# RadioHTC_STM_v3_top_cpu.net
KiCad netlist of a schematic drawn in EAGLE
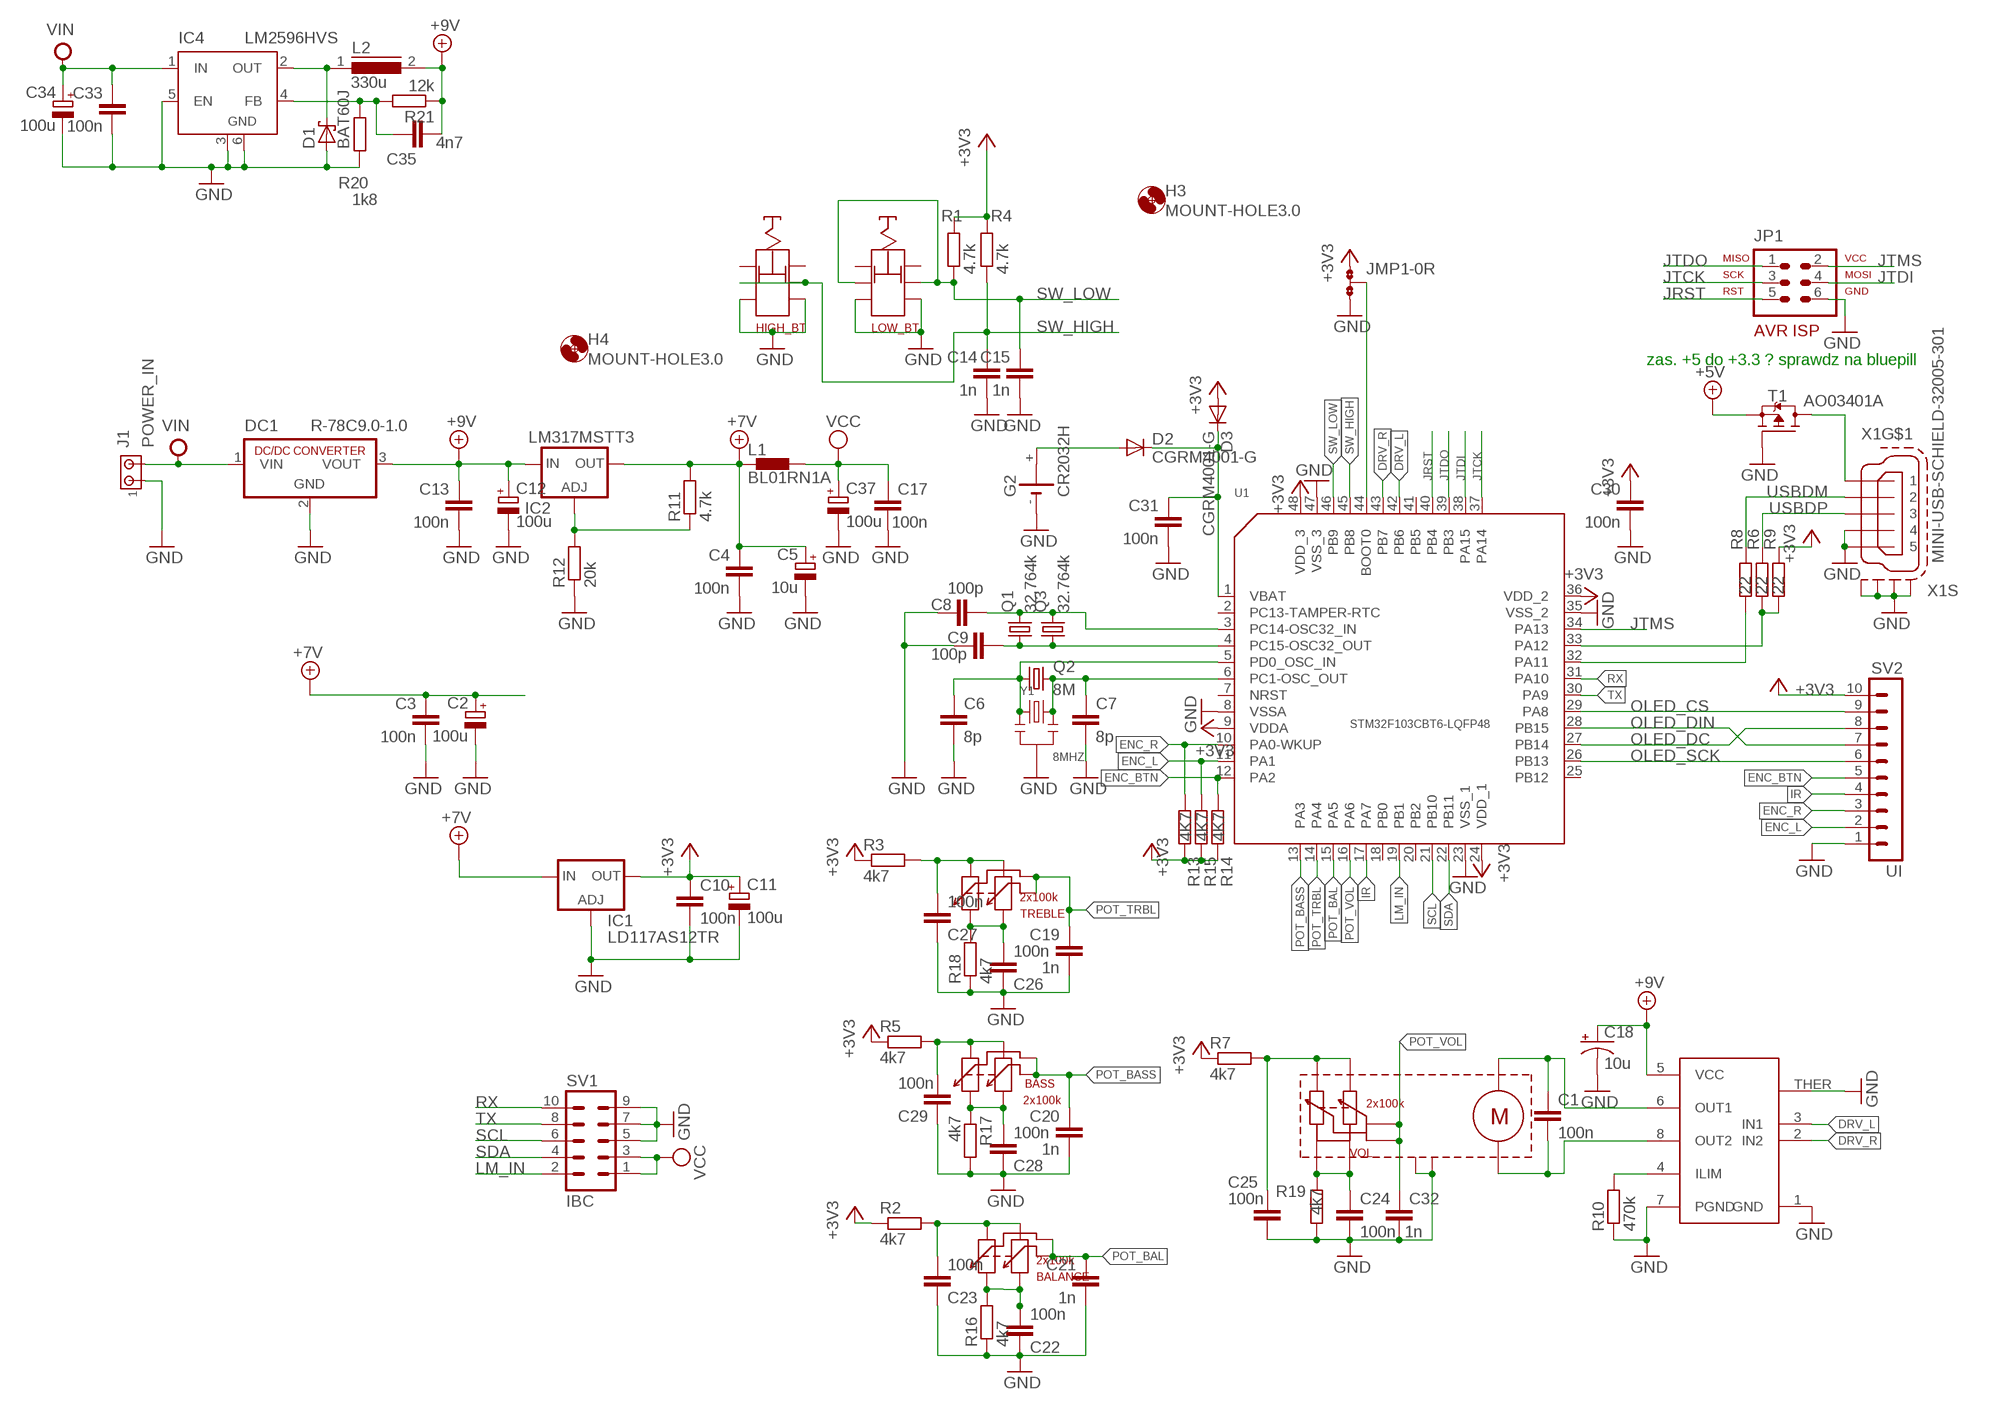
[diagram p0: schematic, sheet 1]

(export (version "E")
  (design (tool "Eeschema 10.0.6"))
  (components
    (comp (ref "BALANCE")
      (value "2x100k")
      (footprint "eagle-import:POT_VERT_DOUBLE")
      (libsource (lib "eagle-import") (part "POT_TONSIL"))
    )
    (comp (ref "BASS")
      (value "2x100k")
      (footprint "eagle-import:POT_VERT_DOUBLE")
      (libsource (lib "eagle-import") (part "POT_TONSIL"))
    )
    (comp (ref "C1")
      (value "100n")
      (footprint "eagle-import:C1206")
      (libsource (lib "eagle-import") (part "C-EUC1206"))
    )
    (comp (ref "C2")
      (value "100u")
      (footprint "eagle-import:E2-5")
      (libsource (lib "eagle-import") (part "CPOL-EUE2-5"))
    )
    (comp (ref "C3")
      (value "100n")
      (footprint "eagle-import:C1206")
      (libsource (lib "eagle-import") (part "C-EUC1206"))
    )
    (comp (ref "C4")
      (value "100n")
      (footprint "eagle-import:C1206")
      (libsource (lib "eagle-import") (part "C-EUC1206"))
    )
    (comp (ref "C5")
      (value "10u")
      (footprint "eagle-import:E2-5")
      (libsource (lib "eagle-import") (part "CPOL-EUE2-5"))
    )
    (comp (ref "C6")
      (value "8p")
      (footprint "eagle-import:C0805K")
      (libsource (lib "eagle-import") (part "C-EUC0805K"))
    )
    (comp (ref "C7")
      (value "8p")
      (footprint "eagle-import:C0805K")
      (libsource (lib "eagle-import") (part "C-EUC0805K"))
    )
    (comp (ref "C8")
      (value "100p")
      (footprint "eagle-import:C0805K")
      (libsource (lib "eagle-import") (part "C-EUC0805K"))
    )
    (comp (ref "C9")
      (value "100p")
      (footprint "eagle-import:C0805K")
      (libsource (lib "eagle-import") (part "C-EUC0805K"))
    )
    (comp (ref "C10")
      (value "100n")
      (footprint "eagle-import:C1206")
      (libsource (lib "eagle-import") (part "C-EUC1206"))
    )
    (comp (ref "C11")
      (value "100u")
      (footprint "eagle-import:E2-5")
      (libsource (lib "eagle-import") (part "CPOL-EUE2-5"))
    )
    (comp (ref "C12")
      (value "100u")
      (footprint "eagle-import:153CLV-0605")
      (libsource (lib "eagle-import") (part "CPOL-EU153CLV-0605"))
    )
    (comp (ref "C13")
      (value "100n")
      (footprint "eagle-import:C1206")
      (libsource (lib "eagle-import") (part "C-EUC1206"))
    )
    (comp (ref "C14")
      (value "1n")
      (footprint "eagle-import:C1206")
      (libsource (lib "eagle-import") (part "C-EUC1206"))
    )
    (comp (ref "C15")
      (value "1n")
      (footprint "eagle-import:C1206")
      (libsource (lib "eagle-import") (part "C-EUC1206"))
    )
    (comp (ref "C17")
      (value "100n")
      (footprint "eagle-import:C1206")
      (libsource (lib "eagle-import") (part "C-EUC1206"))
    )
    (comp (ref "C18")
      (value "10u")
      (footprint "eagle-import:153CLV-0810")
      (libsource (lib "eagle-import") (part "CPOL-US153CLV-0810"))
    )
    (comp (ref "C19")
      (value "1n")
      (footprint "eagle-import:C1206")
      (libsource (lib "eagle-import") (part "C-EUC1206"))
    )
    (comp (ref "C20")
      (value "1n")
      (footprint "eagle-import:C1206")
      (libsource (lib "eagle-import") (part "C-EUC1206"))
    )
    (comp (ref "C21")
      (value "1n")
      (footprint "eagle-import:C1206")
      (libsource (lib "eagle-import") (part "C-EUC1206"))
    )
    (comp (ref "C22")
      (value "100n")
      (footprint "eagle-import:C1206")
      (libsource (lib "eagle-import") (part "C-EUC1206"))
    )
    (comp (ref "C23")
      (value "100n")
      (footprint "eagle-import:C1206")
      (libsource (lib "eagle-import") (part "C-EUC1206"))
    )
    (comp (ref "C24")
      (value "100n")
      (footprint "eagle-import:C1206")
      (libsource (lib "eagle-import") (part "C-EUC1206"))
    )
    (comp (ref "C25")
      (value "100n")
      (footprint "eagle-import:C1206")
      (libsource (lib "eagle-import") (part "C-EUC1206"))
    )
    (comp (ref "C26")
      (value "100n")
      (footprint "eagle-import:C1206")
      (libsource (lib "eagle-import") (part "C-EUC1206"))
    )
    (comp (ref "C27")
      (value "100n")
      (footprint "eagle-import:C1206")
      (libsource (lib "eagle-import") (part "C-EUC1206"))
    )
    (comp (ref "C28")
      (value "100n")
      (footprint "eagle-import:C1206")
      (libsource (lib "eagle-import") (part "C-EUC1206"))
    )
    (comp (ref "C29")
      (value "100n")
      (footprint "eagle-import:C1206")
      (libsource (lib "eagle-import") (part "C-EUC1206"))
    )
    (comp (ref "C30")
      (value "100n")
      (footprint "eagle-import:C1206")
      (libsource (lib "eagle-import") (part "C-EUC1206"))
    )
    (comp (ref "C31")
      (value "100n")
      (footprint "eagle-import:C1206")
      (libsource (lib "eagle-import") (part "C-EUC1206"))
    )
    (comp (ref "C32")
      (value "1n")
      (footprint "eagle-import:C1206")
      (libsource (lib "eagle-import") (part "C-EUC1206"))
    )
    (comp (ref "C33")
      (value "100n")
      (footprint "eagle-import:C1206")
      (libsource (lib "eagle-import") (part "C-EUC1206"))
    )
    (comp (ref "C34")
      (value "100u")
      (footprint "eagle-import:E2-5")
      (libsource (lib "eagle-import") (part "CPOL-EUE2-5"))
    )
    (comp (ref "C35")
      (value "4n7")
      (footprint "eagle-import:C1206")
      (libsource (lib "eagle-import") (part "C-EUC1206"))
    )
    (comp (ref "C37")
      (value "100u")
      (footprint "eagle-import:153CLV-0405")
      (libsource (lib "eagle-import") (part "CPOL-EU153CLV-0405"))
    )
    (comp (ref "D1")
      (value "BAT60J")
      (footprint "eagle-import:SOD323_ST")
      (libsource (lib "eagle-import") (part "BAT60J"))
    )
    (comp (ref "D2")
      (value "CGRM4001-G")
      (footprint "eagle-import:SOD-123_MINI-SMA")
      (libsource (lib "eagle-import") (part "CGRM400-G1"))
    )
    (comp (ref "D3")
      (value "CGRM4001-G")
      (footprint "eagle-import:SOD-123_MINI-SMA")
      (libsource (lib "eagle-import") (part "CGRM400-G1"))
    )
    (comp (ref "DC1")
      (value "R-78C9.0-1.0")
      (footprint "eagle-import:SIP3")
      (libsource (lib "eagle-import") (part "R-78C-1.09.0"))
    )
    (comp (ref "G2")
      (value "CR2032H")
      (footprint "eagle-import:CR2032H")
      (libsource (lib "eagle-import") (part "CR2032H"))
    )
    (comp (ref "H3")
      (value "MOUNT-HOLE3.0")
      (footprint "eagle-import:3,0")
      (libsource (lib "eagle-import") (part "MOUNT-HOLE3.0"))
    )
    (comp (ref "H4")
      (value "MOUNT-HOLE3.0")
      (footprint "eagle-import:3,0")
      (libsource (lib "eagle-import") (part "MOUNT-HOLE3.0"))
    )
    (comp (ref "IC1")
      (value "LD117AS12TR")
      (footprint "eagle-import:SOT223")
      (libsource (lib "eagle-import") (part "LD117A?S12TR"))
    )
    (comp (ref "IC2")
      (value "LM317MSTT3")
      (footprint "eagle-import:SOT223")
      (libsource (lib "eagle-import") (part "LM317?MSTT3"))
    )
    (comp (ref "IC4")
      (value "LM2596HVS")
      (footprint "eagle-import:TO263-5")
      (libsource (lib "eagle-import") (part "LM2596S"))
    )
    (comp (ref "J1")
      (value "POWER_IN")
      (footprint "eagle-import:1X2MTA")
      (libsource (lib "eagle-import") (part "MTA02-156"))
    )
    (comp (ref "JMP1")
      (value "0R-JUMPA")
      (footprint "eagle-import:A0R-JMP")
      (libsource (lib "eagle-import") (part "0R-JUMPA"))
    )
    (comp (ref "JP1")
      (value "AVR-ISP-6VERT")
      (footprint "eagle-import:AVR-ISP-6")
      (libsource (lib "eagle-import") (part "AVR-ISP-6VERT"))
    )
    (comp (ref "L1")
      (value "BL01RN1A")
      (footprint "eagle-import:BL01RN1A")
      (libsource (lib "eagle-import") (part "BL01RN1A"))
    )
    (comp (ref "L2")
      (value "330u")
      (footprint "eagle-import:DR74")
      (libsource (lib "eagle-import") (part "DR74"))
    )
    (comp (ref "Q1")
      (value "32.764k")
      (footprint "eagle-import:MM39SL")
      (libsource (lib "eagle-import") (part "CRYSTALMM39SL"))
    )
    (comp (ref "Q2")
      (value "8M")
      (footprint "eagle-import:HC49U-V")
      (libsource (lib "eagle-import") (part "CRYSTALHC49U-V"))
    )
    (comp (ref "Q3")
      (value "32.764k")
      (footprint "eagle-import:MM20SS")
      (libsource (lib "eagle-import") (part "CRYSTALMM20SS"))
    )
    (comp (ref "R1")
      (value "4.7k")
      (footprint "eagle-import:R1206")
      (libsource (lib "eagle-import") (part "R-EU_R1206"))
    )
    (comp (ref "R2")
      (value "4k7")
      (footprint "eagle-import:R1206")
      (libsource (lib "eagle-import") (part "R-EU_R1206"))
    )
    (comp (ref "R3")
      (value "4k7")
      (footprint "eagle-import:R1206")
      (libsource (lib "eagle-import") (part "R-EU_R1206"))
    )
    (comp (ref "R4")
      (value "4.7k")
      (footprint "eagle-import:R1206")
      (libsource (lib "eagle-import") (part "R-EU_R1206"))
    )
    (comp (ref "R5")
      (value "4k7")
      (footprint "eagle-import:R1206")
      (libsource (lib "eagle-import") (part "R-EU_R1206"))
    )
    (comp (ref "R6")
      (value "22")
      (footprint "eagle-import:R1206")
      (libsource (lib "eagle-import") (part "R-EU_R1206"))
    )
    (comp (ref "R7")
      (value "4k7")
      (footprint "eagle-import:R1206")
      (libsource (lib "eagle-import") (part "R-EU_R1206"))
    )
    (comp (ref "R8")
      (value "22")
      (footprint "eagle-import:R1206")
      (libsource (lib "eagle-import") (part "R-EU_R1206"))
    )
    (comp (ref "R9")
      (value "22")
      (footprint "eagle-import:R1206")
      (libsource (lib "eagle-import") (part "R-EU_R1206"))
    )
    (comp (ref "R10")
      (value "470k")
      (footprint "eagle-import:R1206")
      (libsource (lib "eagle-import") (part "R-EU_R1206"))
    )
    (comp (ref "R11")
      (value "4.7k")
      (footprint "eagle-import:R1206")
      (libsource (lib "eagle-import") (part "R-EU_R1206"))
    )
    (comp (ref "R12")
      (value "20k")
      (footprint "eagle-import:R1206")
      (libsource (lib "eagle-import") (part "R-EU_R1206"))
    )
    (comp (ref "R13")
      (value "4K7")
      (footprint "eagle-import:R1206")
      (libsource (lib "eagle-import") (part "R-EU_R1206"))
    )
    (comp (ref "R14")
      (value "4K7")
      (footprint "eagle-import:R1206")
      (libsource (lib "eagle-import") (part "R-EU_R1206"))
    )
    (comp (ref "R15")
      (value "4K7")
      (footprint "eagle-import:R1206")
      (libsource (lib "eagle-import") (part "R-EU_R1206"))
    )
    (comp (ref "R16")
      (value "4k7")
      (footprint "eagle-import:R1206")
      (libsource (lib "eagle-import") (part "R-EU_R1206"))
    )
    (comp (ref "R17")
      (value "4k7")
      (footprint "eagle-import:R1206")
      (libsource (lib "eagle-import") (part "R-EU_R1206"))
    )
    (comp (ref "R18")
      (value "4k7")
      (footprint "eagle-import:R1206")
      (libsource (lib "eagle-import") (part "R-EU_R1206"))
    )
    (comp (ref "R19")
      (value "4k7")
      (footprint "eagle-import:R1206")
      (libsource (lib "eagle-import") (part "R-EU_R1206"))
    )
    (comp (ref "R20")
      (value "1k8")
      (footprint "eagle-import:R1206")
      (libsource (lib "eagle-import") (part "R-EU_R1206"))
    )
    (comp (ref "R21")
      (value "12k")
      (footprint "eagle-import:R1206")
      (libsource (lib "eagle-import") (part "R-EU_R1206"))
    )
    (comp (ref "SV1")
      (value "IBC")
      (footprint "eagle-import:ML10")
      (libsource (lib "eagle-import") (part "ML10"))
    )
    (comp (ref "SV2")
      (value "UI")
      (footprint "eagle-import:MA10-1W")
      (libsource (lib "eagle-import") (part "MA10-1W"))
    )
    (comp (ref "SW4")
      (value "LOW_BT")
      (footprint "eagle-import:ISO3")
      (libsource (lib "eagle-import") (part "ISO3"))
    )
    (comp (ref "SW6")
      (value "HIGH_BT")
      (footprint "eagle-import:ISO3")
      (libsource (lib "eagle-import") (part "ISO3"))
    )
    (comp (ref "T1")
      (value "AO03401A")
      (footprint "eagle-import:SOT23-R")
      (libsource (lib "eagle-import") (part "P-MOSFET"))
    )
    (comp (ref "TREBLE")
      (value "2x100k")
      (footprint "eagle-import:POT_VERT_DOUBLE")
      (libsource (lib "eagle-import") (part "POT_TONSIL"))
    )
    (comp (ref "U1")
      (value "STM32F103CBT6-LQFP48")
      (footprint "eagle-import:LQFP48-0.5-7X7MM")
      (fields (field (name "MPN") "STM32F103CBT6"))
      (libsource (lib "eagle-import") (part "MCU-STM32F103CBT6(LQFP48)"))
    )
    (comp (ref "U2")
      (value "DRV8871")
      (footprint "eagle-import:DRV8871")
      (libsource (lib "eagle-import") (part "DRV8871"))
    )
    (comp (ref "VOL")
      (value "2x100k")
      (footprint "eagle-import:POT_DOUBLE_MOTOR")
      (libsource (lib "eagle-import") (part "POT_DOUBLE_MOTOR"))
    )
    (comp (ref "X1")
      (value "MINI-USB-SCHIELD-32005-301")
      (footprint "eagle-import:32005-301")
      (libsource (lib "eagle-import") (part "MINI-USB-SCHIELD-32005-301"))
    )
    (comp (ref "Y1")
      (value "8MHZ")
      (footprint "eagle-import:X3-SMD-3.6X1.3X0.8MM")
      (fields (field (name "MPN") "CSTCE16M0V53-R0"))
      (libsource (lib "eagle-import") (part "SMD-RESONATOR-16MHZ-15PF-0.5%-40R(3P-3.2X1.3MM)"))
    )
  )
  (nets
    (net (code "1") (name "+3V3") (class "Default")
      (node (ref "C10") (pin "1") (pinfunction "1_1") (pintype "passive"))
      (node (ref "C11") (pin "+") (pinfunction "+_+") (pintype "passive"))
      (node (ref "C30") (pin "1") (pinfunction "1_1") (pintype "passive"))
      (node (ref "D3") (pin "A") (pinfunction "A_A") (pintype "passive"))
      (node (ref "IC1") (pin "4") (pinfunction "OUT_4") (pintype "passive"))
      (node (ref "JMP1") (pin "1") (pinfunction "1_1") (pintype "passive"))
      (node (ref "R1") (pin "2") (pinfunction "2_2") (pintype "passive"))
      (node (ref "R13") (pin "2") (pinfunction "2_2") (pintype "passive"))
      (node (ref "R14") (pin "2") (pinfunction "2_2") (pintype "passive"))
      (node (ref "R15") (pin "2") (pinfunction "2_2") (pintype "passive"))
      (node (ref "R2") (pin "1") (pinfunction "1_1") (pintype "passive"))
      (node (ref "R3") (pin "1") (pinfunction "1_1") (pintype "passive"))
      (node (ref "R4") (pin "2") (pinfunction "2_2") (pintype "passive"))
      (node (ref "R5") (pin "1") (pinfunction "1_1") (pintype "passive"))
      (node (ref "R7") (pin "1") (pinfunction "1_1") (pintype "passive"))
      (node (ref "R9") (pin "2") (pinfunction "2_2") (pintype "passive"))
      (node (ref "SV2") (pin "10") (pinfunction "10_10") (pintype "passive"))
      (node (ref "U1") (pin "24") (pinfunction "VDD_1_24") (pintype "bidirectional"))
      (node (ref "U1") (pin "36") (pinfunction "VDD_2_36") (pintype "bidirectional"))
      (node (ref "U1") (pin "48") (pinfunction "VDD_3_48") (pintype "bidirectional"))
      (node (ref "U1") (pin "9") (pinfunction "VDDA_9") (pintype "bidirectional"))
    )
    (net (code "2") (name "+5V") (class "Default")
      (node (ref "T1") (pin "2") (pinfunction "S_2") (pintype "passive"))
    )
    (net (code "3") (name "+7V") (class "Default")
      (node (ref "C2") (pin "+") (pinfunction "+_+") (pintype "passive"))
      (node (ref "C3") (pin "1") (pinfunction "1_1") (pintype "passive"))
      (node (ref "C4") (pin "1") (pinfunction "1_1") (pintype "passive"))
      (node (ref "C5") (pin "+") (pinfunction "+_+") (pintype "passive"))
      (node (ref "IC1") (pin "3") (pinfunction "IN_3") (pintype "input"))
      (node (ref "IC2") (pin "4") (pinfunction "OUT_4") (pintype "passive"))
      (node (ref "L1") (pin "1") (pinfunction "1_1") (pintype "passive"))
      (node (ref "R11") (pin "2") (pinfunction "2_2") (pintype "passive"))
    )
    (net (code "4") (name "+9V") (class "Default")
      (node (ref "C12") (pin "+") (pinfunction "+_+") (pintype "passive"))
      (node (ref "C13") (pin "1") (pinfunction "1_1") (pintype "passive"))
      (node (ref "C18") (pin "+") (pinfunction "+_+") (pintype "passive"))
      (node (ref "C35") (pin "2") (pinfunction "2_2") (pintype "passive"))
      (node (ref "DC1") (pin "3") (pinfunction "VOUT_3") (pintype "passive"))
      (node (ref "IC2") (pin "3") (pinfunction "IN_3") (pintype "input"))
      (node (ref "L2") (pin "2") (pinfunction "2_2") (pintype "passive"))
      (node (ref "R21") (pin "1") (pinfunction "1_1") (pintype "passive"))
      (node (ref "U2") (pin "5") (pinfunction "VCC_5") (pintype "power_in"))
    )
    (net (code "5") (name "/JRST") (class "Default")
      (node (ref "JP1") (pin "5") (pinfunction "5_5") (pintype "passive"))
      (node (ref "U1") (pin "40") (pinfunction "PB4_40") (pintype "bidirectional"))
    )
    (net (code "6") (name "/JTCK") (class "Default")
      (node (ref "JP1") (pin "3") (pinfunction "3_3") (pintype "passive"))
      (node (ref "U1") (pin "37") (pinfunction "PA14_37") (pintype "bidirectional"))
    )
    (net (code "7") (name "/JTDI") (class "Default")
      (node (ref "JP1") (pin "4") (pinfunction "4_4") (pintype "passive"))
      (node (ref "U1") (pin "38") (pinfunction "PA15_38") (pintype "bidirectional"))
    )
    (net (code "8") (name "/JTDO") (class "Default")
      (node (ref "JP1") (pin "1") (pinfunction "1_1") (pintype "passive"))
      (node (ref "U1") (pin "39") (pinfunction "PB3_39") (pintype "bidirectional"))
    )
    (net (code "9") (name "/JTMS") (class "Default")
      (node (ref "JP1") (pin "2") (pinfunction "2_2") (pintype "passive"))
      (node (ref "U1") (pin "34") (pinfunction "PA13_34") (pintype "bidirectional"))
    )
    (net (code "10") (name "/OLED_CS") (class "Default")
      (node (ref "SV2") (pin "9") (pinfunction "9_9") (pintype "passive"))
      (node (ref "U1") (pin "29") (pinfunction "PA8_29") (pintype "bidirectional"))
    )
    (net (code "11") (name "/OLED_DC") (class "Default")
      (node (ref "SV2") (pin "8") (pinfunction "8_8") (pintype "passive"))
      (node (ref "U1") (pin "27") (pinfunction "PB14_27") (pintype "bidirectional"))
    )
    (net (code "12") (name "/OLED_DIN") (class "Default")
      (node (ref "SV2") (pin "7") (pinfunction "7_7") (pintype "passive"))
      (node (ref "U1") (pin "28") (pinfunction "PB15_28") (pintype "bidirectional"))
    )
    (net (code "13") (name "/OLED_SCK") (class "Default")
      (node (ref "SV2") (pin "6") (pinfunction "6_6") (pintype "passive"))
      (node (ref "U1") (pin "26") (pinfunction "PB13_26") (pintype "bidirectional"))
    )
    (net (code "14") (name "/USBDM") (class "Default")
      (node (ref "R8") (pin "2") (pinfunction "2_2") (pintype "passive"))
      (node (ref "X1") (pin "2") (pinfunction "2_2") (pintype "passive"))
    )
    (net (code "15") (name "/USBDP") (class "Default")
      (node (ref "R6") (pin "2") (pinfunction "2_2") (pintype "passive"))
      (node (ref "X1") (pin "3") (pinfunction "3_3") (pintype "passive"))
    )
    (net (code "16") (name "DRV_L") (class "Default")
      (node (ref "U1") (pin "42") (pinfunction "PB6_42") (pintype "bidirectional"))
      (node (ref "U2") (pin "3") (pinfunction "IN1_3") (pintype "input"))
    )
    (net (code "17") (name "DRV_R") (class "Default")
      (node (ref "U1") (pin "43") (pinfunction "PB7_43") (pintype "bidirectional"))
      (node (ref "U2") (pin "2") (pinfunction "IN2_2") (pintype "input"))
    )
    (net (code "18") (name "ENC_BTN") (class "Default")
      (node (ref "R14") (pin "1") (pinfunction "1_1") (pintype "passive"))
      (node (ref "SV2") (pin "5") (pinfunction "5_5") (pintype "passive"))
      (node (ref "U1") (pin "12") (pinfunction "PA2_12") (pintype "bidirectional"))
    )
    (net (code "19") (name "ENC_L") (class "Default")
      (node (ref "R15") (pin "1") (pinfunction "1_1") (pintype "passive"))
      (node (ref "SV2") (pin "2") (pinfunction "2_2") (pintype "passive"))
      (node (ref "U1") (pin "11") (pinfunction "PA1_11") (pintype "bidirectional"))
    )
    (net (code "20") (name "ENC_R") (class "Default")
      (node (ref "R13") (pin "1") (pinfunction "1_1") (pintype "passive"))
      (node (ref "SV2") (pin "3") (pinfunction "3_3") (pintype "passive"))
      (node (ref "U1") (pin "10") (pinfunction "PA0-WKUP_10") (pintype "bidirectional"))
    )
    (net (code "21") (name "GND") (class "Default")
      (node (ref "C10") (pin "2") (pinfunction "2_2") (pintype "passive"))
      (node (ref "C11") (pin "-") (pinfunction "-_-") (pintype "passive"))
      (node (ref "C12") (pin "-") (pinfunction "-_-") (pintype "passive"))
      (node (ref "C13") (pin "2") (pinfunction "2_2") (pintype "passive"))
      (node (ref "C14") (pin "2") (pinfunction "2_2") (pintype "passive"))
      (node (ref "C15") (pin "2") (pinfunction "2_2") (pintype "passive"))
      (node (ref "C17") (pin "2") (pinfunction "2_2") (pintype "passive"))
      (node (ref "C18") (pin "-") (pinfunction "-_-") (pintype "passive"))
      (node (ref "C19") (pin "2") (pinfunction "2_2") (pintype "passive"))
      (node (ref "C2") (pin "-") (pinfunction "-_-") (pintype "passive"))
      (node (ref "C20") (pin "2") (pinfunction "2_2") (pintype "passive"))
      (node (ref "C21") (pin "2") (pinfunction "2_2") (pintype "passive"))
      (node (ref "C22") (pin "1") (pinfunction "1_1") (pintype "passive"))
      (node (ref "C23") (pin "1") (pinfunction "1_1") (pintype "passive"))
      (node (ref "C24") (pin "1") (pinfunction "1_1") (pintype "passive"))
      (node (ref "C25") (pin "1") (pinfunction "1_1") (pintype "passive"))
      (node (ref "C26") (pin "1") (pinfunction "1_1") (pintype "passive"))
      (node (ref "C27") (pin "1") (pinfunction "1_1") (pintype "passive"))
      (node (ref "C28") (pin "1") (pinfunction "1_1") (pintype "passive"))
      (node (ref "C29") (pin "1") (pinfunction "1_1") (pintype "passive"))
      (node (ref "C3") (pin "2") (pinfunction "2_2") (pintype "passive"))
      (node (ref "C30") (pin "2") (pinfunction "2_2") (pintype "passive"))
      (node (ref "C31") (pin "2") (pinfunction "2_2") (pintype "passive"))
      (node (ref "C32") (pin "2") (pinfunction "2_2") (pintype "passive"))
      (node (ref "C33") (pin "2") (pinfunction "2_2") (pintype "passive"))
      (node (ref "C34") (pin "-") (pinfunction "-_-") (pintype "passive"))
      (node (ref "C37") (pin "-") (pinfunction "-_-") (pintype "passive"))
      (node (ref "C4") (pin "2") (pinfunction "2_2") (pintype "passive"))
      (node (ref "C5") (pin "-") (pinfunction "-_-") (pintype "passive"))
      (node (ref "C6") (pin "2") (pinfunction "2_2") (pintype "passive"))
      (node (ref "C7") (pin "2") (pinfunction "2_2") (pintype "passive"))
      (node (ref "C8") (pin "2") (pinfunction "2_2") (pintype "passive"))
      (node (ref "C9") (pin "1") (pinfunction "1_1") (pintype "passive"))
      (node (ref "D1") (pin "A") (pinfunction "A_A") (pintype "passive"))
      (node (ref "DC1") (pin "2") (pinfunction "GND_2") (pintype "passive"))
      (node (ref "G2") (pin "-") (pinfunction "-_-") (pintype "passive"))
      (node (ref "IC1") (pin "1") (pinfunction "ADJ_1") (pintype "input"))
      (node (ref "IC4") (pin "3") (pinfunction "GND_3") (pintype "power_in"))
      (node (ref "IC4") (pin "5") (pinfunction "EN_5") (pintype "input"))
      (node (ref "IC4") (pin "6") (pinfunction "GND_6") (pintype "power_in"))
      (node (ref "J1") (pin "1") (pinfunction "1_1") (pintype "passive"))
      (node (ref "JMP1") (pin "3") (pinfunction "3_3") (pintype "passive"))
      (node (ref "JP1") (pin "6") (pinfunction "6_6") (pintype "passive"))
      (node (ref "R10") (pin "1") (pinfunction "1_1") (pintype "passive"))
      (node (ref "R12") (pin "1") (pinfunction "1_1") (pintype "passive"))
      (node (ref "R16") (pin "1") (pinfunction "1_1") (pintype "passive"))
      (node (ref "R17") (pin "2") (pinfunction "2_2") (pintype "passive"))
      (node (ref "R18") (pin "1") (pinfunction "1_1") (pintype "passive"))
      (node (ref "R19") (pin "1") (pinfunction "1_1") (pintype "passive"))
      (node (ref "R20") (pin "1") (pinfunction "1_1") (pintype "passive"))
      (node (ref "SV1") (pin "5") (pinfunction "5_5") (pintype "passive"))
      (node (ref "SV1") (pin "7") (pinfunction "7_7") (pintype "passive"))
      (node (ref "SV1") (pin "9") (pinfunction "9_9") (pintype "passive"))
      (node (ref "SV2") (pin "1") (pinfunction "1_1") (pintype "passive"))
      (node (ref "SW4") (pin "P$3") (pinfunction "P$3_P$3") (pintype "bidirectional"))
      (node (ref "SW4") (pin "P$4") (pinfunction "P$4_P$4") (pintype "bidirectional"))
      (node (ref "SW6") (pin "P$3") (pinfunction "P$3_P$3") (pintype "bidirectional"))
      (node (ref "SW6") (pin "P$4") (pinfunction "P$4_P$4") (pintype "bidirectional"))
      (node (ref "T1") (pin "1") (pinfunction "G_1") (pintype "passive"))
      (node (ref "U1") (pin "23") (pinfunction "VSS_1_23") (pintype "bidirectional"))
      (node (ref "U1") (pin "35") (pinfunction "VSS_2_35") (pintype "bidirectional"))
      (node (ref "U1") (pin "47") (pinfunction "VSS_3_47") (pintype "bidirectional"))
      (node (ref "U1") (pin "8") (pinfunction "VSSA_8") (pintype "bidirectional"))
      (node (ref "U2") (pin "1") (pinfunction "GND_1") (pintype "power_in"))
      (node (ref "U2") (pin "7") (pinfunction "PGND_7") (pintype "power_in"))
      (node (ref "U2") (pin "THER") (pinfunction "GND_THER") (pintype "power_in"))
      (node (ref "VOL") (pin "P$10") (pinfunction "G_P$10") (pintype "bidirectional"))
      (node (ref "VOL") (pin "P$9") (pinfunction "G_P$9") (pintype "bidirectional"))
      (node (ref "X1") (pin "4") (pinfunction "4_4") (pintype "passive"))
      (node (ref "X1") (pin "5") (pinfunction "5_5") (pintype "passive"))
      (node (ref "X1") (pin "M1") (pinfunction "S1_M1") (pintype "passive"))
      (node (ref "X1") (pin "M2") (pinfunction "S2_M2") (pintype "passive"))
      (node (ref "X1") (pin "M3") (pinfunction "S3_M3") (pintype "passive"))
      (node (ref "X1") (pin "M4") (pinfunction "S4_M4") (pintype "passive"))
      (node (ref "Y1") (pin "2") (pinfunction "2_2") (pintype "passive"))
    )
    (net (code "22") (name "IR") (class "Default")
      (node (ref "SV2") (pin "4") (pinfunction "4_4") (pintype "passive"))
      (node (ref "U1") (pin "17") (pinfunction "PA7_17") (pintype "bidirectional"))
    )
    (net (code "23") (name "LM_IN") (class "Default")
      (node (ref "SV1") (pin "2") (pinfunction "2_2") (pintype "passive"))
      (node (ref "U1") (pin "19") (pinfunction "PB1_19") (pintype "bidirectional"))
    )
    (net (code "24") (name "Net-(BALANCE-PadA1)") (class "Default")
      (node (ref "BALANCE") (pin "A1") (pinfunction "A1_A1") (pintype "passive"))
      (node (ref "BALANCE") (pin "A2") (pinfunction "A2_A2") (pintype "passive"))
      (node (ref "C23") (pin "2") (pinfunction "2_2") (pintype "passive"))
      (node (ref "R2") (pin "2") (pinfunction "2_2") (pintype "passive"))
    )
    (net (code "25") (name "Net-(BALANCE-PadB1)") (class "Default")
      (node (ref "BALANCE") (pin "B1") (pinfunction "B1_B1") (pintype "passive"))
      (node (ref "BALANCE") (pin "B2") (pinfunction "B2_B2") (pintype "passive"))
      (node (ref "C22") (pin "2") (pinfunction "2_2") (pintype "passive"))
      (node (ref "R16") (pin "2") (pinfunction "2_2") (pintype "passive"))
    )
    (net (code "26") (name "Net-(BASS-PadA1)") (class "Default")
      (node (ref "BASS") (pin "A1") (pinfunction "A1_A1") (pintype "passive"))
      (node (ref "BASS") (pin "A2") (pinfunction "A2_A2") (pintype "passive"))
      (node (ref "C29") (pin "2") (pinfunction "2_2") (pintype "passive"))
      (node (ref "R5") (pin "2") (pinfunction "2_2") (pintype "passive"))
    )
    (net (code "27") (name "Net-(BASS-PadB1)") (class "Default")
      (node (ref "BASS") (pin "B1") (pinfunction "B1_B1") (pintype "passive"))
      (node (ref "BASS") (pin "B2") (pinfunction "B2_B2") (pintype "passive"))
      (node (ref "C28") (pin "2") (pinfunction "2_2") (pintype "passive"))
      (node (ref "R17") (pin "1") (pinfunction "1_1") (pintype "passive"))
    )
    (net (code "28") (name "Net-(C24-Pad2)") (class "Default")
      (node (ref "C24") (pin "2") (pinfunction "2_2") (pintype "passive"))
      (node (ref "R19") (pin "2") (pinfunction "2_2") (pintype "passive"))
      (node (ref "VOL") (pin "P$5") (pinfunction "P$5_P$5") (pintype "passive"))
      (node (ref "VOL") (pin "P$6") (pinfunction "P$6_P$6") (pintype "passive"))
    )
    (net (code "29") (name "Net-(C25-Pad2)") (class "Default")
      (node (ref "C25") (pin "2") (pinfunction "2_2") (pintype "passive"))
      (node (ref "R7") (pin "2") (pinfunction "2_2") (pintype "passive"))
      (node (ref "VOL") (pin "P$2") (pinfunction "P$2_P$2") (pintype "passive"))
      (node (ref "VOL") (pin "P$3") (pinfunction "P$3_P$3") (pintype "passive"))
    )
    (net (code "30") (name "Net-(C26-Pad2)") (class "Default")
      (node (ref "C26") (pin "2") (pinfunction "2_2") (pintype "passive"))
      (node (ref "R18") (pin "2") (pinfunction "2_2") (pintype "passive"))
      (node (ref "TREBLE") (pin "B1") (pinfunction "B1_B1") (pintype "passive"))
      (node (ref "TREBLE") (pin "B2") (pinfunction "B2_B2") (pintype "passive"))
    )
    (net (code "31") (name "Net-(C27-Pad2)") (class "Default")
      (node (ref "C27") (pin "2") (pinfunction "2_2") (pintype "passive"))
      (node (ref "R3") (pin "2") (pinfunction "2_2") (pintype "passive"))
      (node (ref "TREBLE") (pin "A1") (pinfunction "A1_A1") (pintype "passive"))
      (node (ref "TREBLE") (pin "A2") (pinfunction "A2_A2") (pintype "passive"))
    )
    (net (code "32") (name "Net-(D2-PadA)") (class "Default")
      (node (ref "D2") (pin "A") (pinfunction "A_A") (pintype "passive"))
      (node (ref "G2") (pin "+") (pinfunction "+_+") (pintype "passive"))
    )
    (net (code "33") (name "Net-(IC2-ADJ)") (class "Default")
      (node (ref "IC2") (pin "1") (pinfunction "ADJ_1") (pintype "input"))
      (node (ref "R11") (pin "1") (pinfunction "1_1") (pintype "passive"))
      (node (ref "R12") (pin "2") (pinfunction "2_2") (pintype "passive"))
    )
    (net (code "34") (name "Net-(IC4-FB)") (class "Default")
      (node (ref "C35") (pin "1") (pinfunction "1_1") (pintype "passive"))
      (node (ref "IC4") (pin "4") (pinfunction "FB_4") (pintype "input"))
      (node (ref "R20") (pin "2") (pinfunction "2_2") (pintype "passive"))
      (node (ref "R21") (pin "2") (pinfunction "2_2") (pintype "passive"))
    )
    (net (code "35") (name "Net-(IC4-OUT)") (class "Default")
      (node (ref "D1") (pin "C") (pinfunction "C_C") (pintype "passive"))
      (node (ref "IC4") (pin "2") (pinfunction "OUT_2") (pintype "output"))
      (node (ref "L2") (pin "1") (pinfunction "1_1") (pintype "passive"))
    )
    (net (code "36") (name "Net-(Q1-2)") (class "Default")
      (node (ref "C8") (pin "1") (pinfunction "1_1") (pintype "passive"))
      (node (ref "Q1") (pin "4") (pinfunction "2_4") (pintype "passive"))
      (node (ref "Q3") (pin "4") (pinfunction "2_4") (pintype "passive"))
      (node (ref "U1") (pin "3") (pinfunction "PC14-OSC32_IN_3") (pintype "bidirectional"))
    )
    (net (code "37") (name "Net-(T1-D)") (class "Default")
      (node (ref "T1") (pin "3") (pinfunction "D_3") (pintype "passive"))
      (node (ref "X1") (pin "1") (pinfunction "1_1") (pintype "passive"))
    )
    (net (code "38") (name "Net-(U1-BOOT0)") (class "Default")
      (node (ref "JMP1") (pin "2") (pinfunction "2_2") (pintype "passive"))
      (node (ref "U1") (pin "44") (pinfunction "BOOT0_44") (pintype "bidirectional"))
    )
    (net (code "39") (name "Net-(U1-PA11)") (class "Default")
      (node (ref "R8") (pin "1") (pinfunction "1_1") (pintype "passive"))
      (node (ref "U1") (pin "32") (pinfunction "PA11_32") (pintype "bidirectional"))
    )
    (net (code "40") (name "Net-(U1-PA12)") (class "Default")
      (node (ref "R6") (pin "1") (pinfunction "1_1") (pintype "passive"))
      (node (ref "R9") (pin "1") (pinfunction "1_1") (pintype "passive"))
      (node (ref "U1") (pin "33") (pinfunction "PA12_33") (pintype "bidirectional"))
    )
    (net (code "41") (name "Net-(U1-PC1-OSC_OUT)") (class "Default")
      (node (ref "C7") (pin "1") (pinfunction "1_1") (pintype "passive"))
      (node (ref "Q2") (pin "2") (pinfunction "2_2") (pintype "passive"))
      (node (ref "U1") (pin "6") (pinfunction "PC1-OSC_OUT_6") (pintype "bidirectional"))
      (node (ref "Y1") (pin "3") (pinfunction "3_3") (pintype "passive"))
    )
    (net (code "42") (name "Net-(U1-PC15-OSC32_OUT)") (class "Default")
      (node (ref "C9") (pin "2") (pinfunction "2_2") (pintype "passive"))
      (node (ref "Q1") (pin "1") (pinfunction "1_1") (pintype "passive"))
      (node (ref "Q3") (pin "1") (pinfunction "1_1") (pintype "passive"))
      (node (ref "U1") (pin "4") (pinfunction "PC15-OSC32_OUT_4") (pintype "bidirectional"))
    )
    (net (code "43") (name "Net-(U1-PD0_OSC_IN)") (class "Default")
      (node (ref "C6") (pin "1") (pinfunction "1_1") (pintype "passive"))
      (node (ref "Q2") (pin "1") (pinfunction "1_1") (pintype "passive"))
      (node (ref "U1") (pin "5") (pinfunction "PD0_OSC_IN_5") (pintype "bidirectional"))
      (node (ref "Y1") (pin "1") (pinfunction "1_1") (pintype "passive"))
    )
    (net (code "44") (name "Net-(U1-VBAT)") (class "Default")
      (node (ref "C31") (pin "1") (pinfunction "1_1") (pintype "passive"))
      (node (ref "D2") (pin "C") (pinfunction "C_C") (pintype "passive"))
      (node (ref "D3") (pin "C") (pinfunction "C_C") (pintype "passive"))
      (node (ref "U1") (pin "1") (pinfunction "VBAT_1") (pintype "bidirectional"))
    )
    (net (code "45") (name "Net-(U2-ILIM)") (class "Default")
      (node (ref "R10") (pin "2") (pinfunction "2_2") (pintype "passive"))
      (node (ref "U2") (pin "4") (pinfunction "ILIM_4") (pintype "output"))
    )
    (net (code "46") (name "Net-(U2-OUT1)") (class "Default")
      (node (ref "C1") (pin "1") (pinfunction "1_1") (pintype "passive"))
      (node (ref "U2") (pin "6") (pinfunction "OUT1_6") (pintype "output"))
      (node (ref "VOL") (pin "M+") (pinfunction "M+_M+") (pintype "bidirectional"))
    )
    (net (code "47") (name "Net-(U2-OUT2)") (class "Default")
      (node (ref "C1") (pin "2") (pinfunction "2_2") (pintype "passive"))
      (node (ref "U2") (pin "8") (pinfunction "OUT2_8") (pintype "output"))
      (node (ref "VOL") (pin "M-") (pinfunction "M-_M-") (pintype "bidirectional"))
    )
    (net (code "48") (name "POT_BAL") (class "Default")
      (node (ref "BALANCE") (pin "C1") (pinfunction "C1_C1") (pintype "passive"))
      (node (ref "BALANCE") (pin "C2") (pinfunction "C2_C2") (pintype "passive"))
      (node (ref "C21") (pin "1") (pinfunction "1_1") (pintype "passive"))
      (node (ref "U1") (pin "15") (pinfunction "PA5_15") (pintype "bidirectional"))
    )
    (net (code "49") (name "POT_BASS") (class "Default")
      (node (ref "BASS") (pin "C1") (pinfunction "C1_C1") (pintype "passive"))
      (node (ref "BASS") (pin "C2") (pinfunction "C2_C2") (pintype "passive"))
      (node (ref "C20") (pin "1") (pinfunction "1_1") (pintype "passive"))
      (node (ref "U1") (pin "13") (pinfunction "PA3_13") (pintype "bidirectional"))
    )
    (net (code "50") (name "POT_TRBL") (class "Default")
      (node (ref "C19") (pin "1") (pinfunction "1_1") (pintype "passive"))
      (node (ref "TREBLE") (pin "C1") (pinfunction "C1_C1") (pintype "passive"))
      (node (ref "TREBLE") (pin "C2") (pinfunction "C2_C2") (pintype "passive"))
      (node (ref "U1") (pin "14") (pinfunction "PA4_14") (pintype "bidirectional"))
    )
    (net (code "51") (name "POT_VOL") (class "Default")
      (node (ref "C32") (pin "1") (pinfunction "1_1") (pintype "passive"))
      (node (ref "U1") (pin "16") (pinfunction "PA6_16") (pintype "bidirectional"))
      (node (ref "VOL") (pin "P$4") (pinfunction "P$4_P$4") (pintype "passive"))
      (node (ref "VOL") (pin "P$7") (pinfunction "P$7_P$7") (pintype "passive"))
    )
    (net (code "52") (name "RX") (class "Default")
      (node (ref "SV1") (pin "10") (pinfunction "10_10") (pintype "passive"))
      (node (ref "U1") (pin "31") (pinfunction "PA10_31") (pintype "bidirectional"))
    )
    (net (code "53") (name "SCL") (class "Default")
      (node (ref "SV1") (pin "6") (pinfunction "6_6") (pintype "passive"))
      (node (ref "U1") (pin "21") (pinfunction "PB10_21") (pintype "bidirectional"))
    )
    (net (code "54") (name "SDA") (class "Default")
      (node (ref "SV1") (pin "4") (pinfunction "4_4") (pintype "passive"))
      (node (ref "U1") (pin "22") (pinfunction "PB11_22") (pintype "bidirectional"))
    )
    (net (code "55") (name "SW_HIGH") (class "Default")
      (node (ref "C14") (pin "1") (pinfunction "1_1") (pintype "passive"))
      (node (ref "R4") (pin "1") (pinfunction "1_1") (pintype "passive"))
      (node (ref "SW6") (pin "P$2") (pinfunction "P$2_P$2") (pintype "bidirectional"))
      (node (ref "SW6") (pin "P$5") (pinfunction "P$5_P$5") (pintype "bidirectional"))
      (node (ref "U1") (pin "45") (pinfunction "PB8_45") (pintype "bidirectional"))
    )
    (net (code "56") (name "SW_LOW") (class "Default")
      (node (ref "C15") (pin "1") (pinfunction "1_1") (pintype "passive"))
      (node (ref "R1") (pin "1") (pinfunction "1_1") (pintype "passive"))
      (node (ref "SW4") (pin "P$2") (pinfunction "P$2_P$2") (pintype "bidirectional"))
      (node (ref "SW4") (pin "P$5") (pinfunction "P$5_P$5") (pintype "bidirectional"))
      (node (ref "U1") (pin "46") (pinfunction "PB9_46") (pintype "bidirectional"))
    )
    (net (code "57") (name "TX") (class "Default")
      (node (ref "SV1") (pin "8") (pinfunction "8_8") (pintype "passive"))
      (node (ref "U1") (pin "30") (pinfunction "PA9_30") (pintype "bidirectional"))
    )
    (net (code "58") (name "VCC") (class "Default")
      (node (ref "C17") (pin "1") (pinfunction "1_1") (pintype "passive"))
      (node (ref "C37") (pin "+") (pinfunction "+_+") (pintype "passive"))
      (node (ref "L1") (pin "2") (pinfunction "2_2") (pintype "passive"))
      (node (ref "SV1") (pin "1") (pinfunction "1_1") (pintype "passive"))
      (node (ref "SV1") (pin "3") (pinfunction "3_3") (pintype "passive"))
    )
    (net (code "59") (name "VIN") (class "Default")
      (node (ref "C33") (pin "1") (pinfunction "1_1") (pintype "passive"))
      (node (ref "C34") (pin "+") (pinfunction "+_+") (pintype "passive"))
      (node (ref "DC1") (pin "1") (pinfunction "VIN_1") (pintype "passive"))
      (node (ref "IC4") (pin "1") (pinfunction "IN_1") (pintype "input"))
      (node (ref "J1") (pin "2") (pinfunction "2_2") (pintype "passive"))
    )
    (net (code "60") (name "unconnected-(SW4-PadP$1)") (class "Default")
      (node (ref "SW4") (pin "P$1") (pinfunction "P$1_P$1") (pintype "bidirectional"))
    )
    (net (code "61") (name "unconnected-(SW4-PadP$6)") (class "Default")
      (node (ref "SW4") (pin "P$6") (pinfunction "P$6_P$6") (pintype "bidirectional"))
    )
    (net (code "62") (name "unconnected-(SW6-PadP$1)") (class "Default")
      (node (ref "SW6") (pin "P$1") (pinfunction "P$1_P$1") (pintype "bidirectional"))
    )
    (net (code "63") (name "unconnected-(SW6-PadP$6)") (class "Default")
      (node (ref "SW6") (pin "P$6") (pinfunction "P$6_P$6") (pintype "bidirectional"))
    )
    (net (code "64") (name "unconnected-(U1-NRST-Pad7)") (class "Default")
      (node (ref "U1") (pin "7") (pinfunction "NRST_7") (pintype "bidirectional"))
    )
    (net (code "65") (name "unconnected-(U1-PB0-Pad18)") (class "Default")
      (node (ref "U1") (pin "18") (pinfunction "PB0_18") (pintype "bidirectional"))
    )
    (net (code "66") (name "unconnected-(U1-PB2-Pad20)") (class "Default")
      (node (ref "U1") (pin "20") (pinfunction "PB2_20") (pintype "bidirectional"))
    )
    (net (code "67") (name "unconnected-(U1-PB5-Pad41)") (class "Default")
      (node (ref "U1") (pin "41") (pinfunction "PB5_41") (pintype "bidirectional"))
    )
    (net (code "68") (name "unconnected-(U1-PB12-Pad25)") (class "Default")
      (node (ref "U1") (pin "25") (pinfunction "PB12_25") (pintype "bidirectional"))
    )
    (net (code "69") (name "unconnected-(U1-PC13-TAMPER-RTC-Pad2)") (class "Default")
      (node (ref "U1") (pin "2") (pinfunction "PC13-TAMPER-RTC_2") (pintype "bidirectional"))
    )
  )
)
